# ICS.net
KiCad netlist of a schematic drawn in Altium Designer
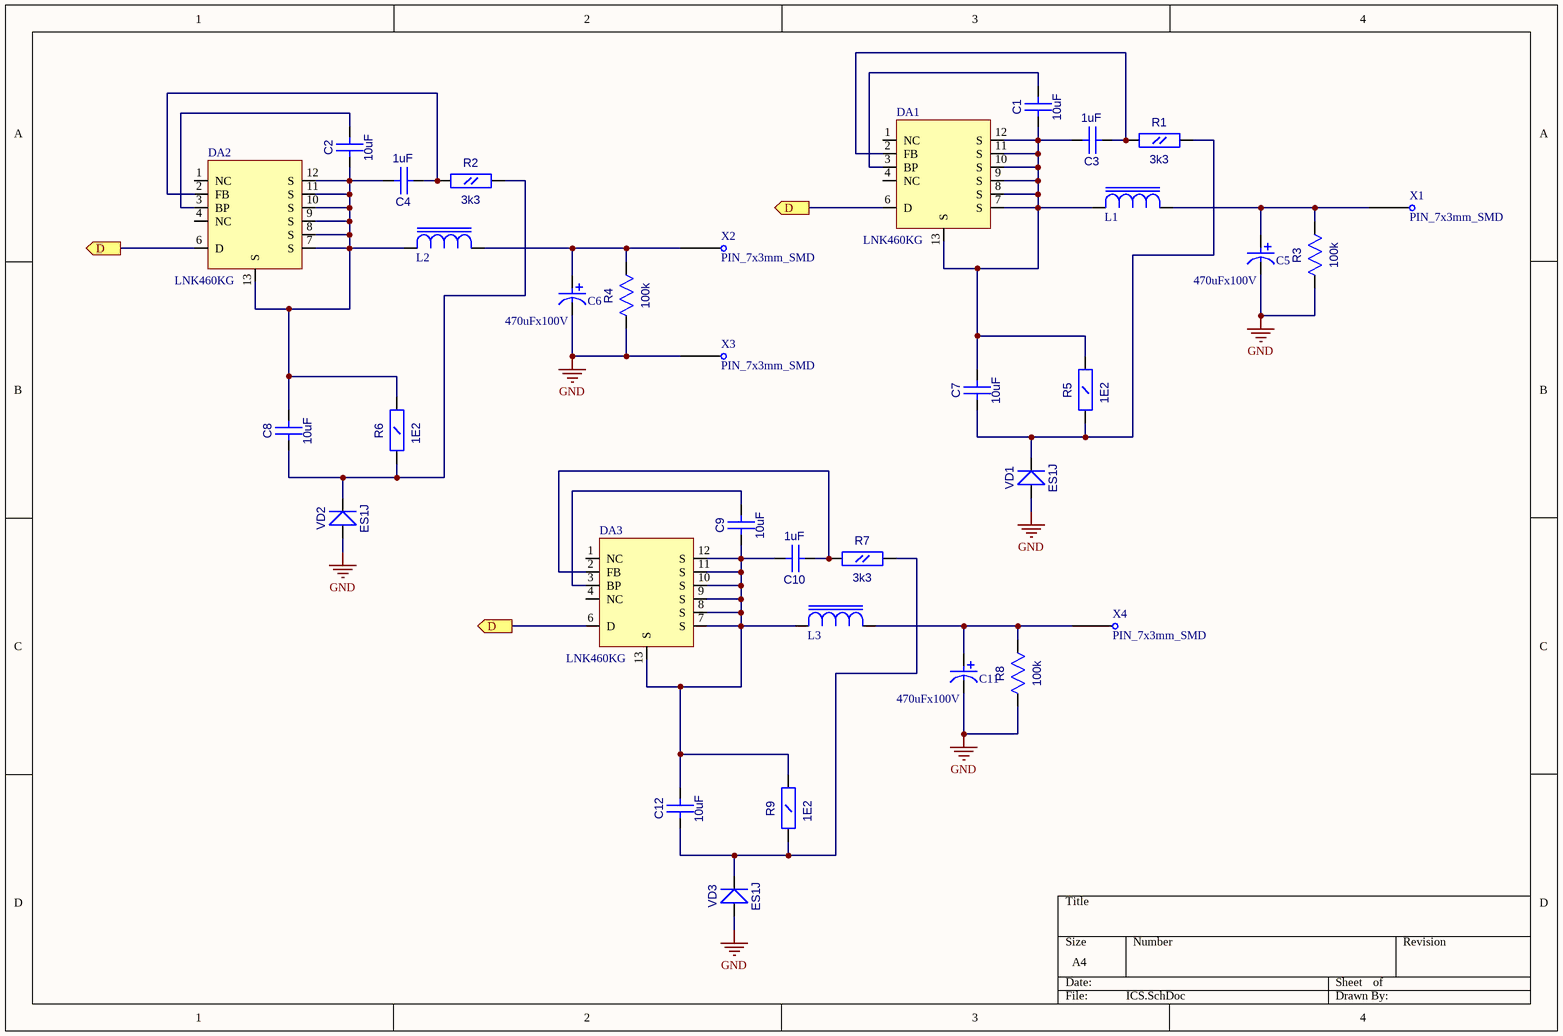
[diagram p0: ICS.SchDoc]

(export (version "E")
  (design (tool "Eeschema 10.0.6"))
  (components
    (comp (ref "C1")
      (value "10uF")
      (footprint "CC1206")
      (description "CC1206")
      (libsource (lib "gprs_modem_2") (part "CC1206"))
    )
    (comp (ref "C2")
      (value "10uF")
      (footprint "CC1206")
      (description "CC1206")
      (libsource (lib "gprs_modem_2") (part "CC1206"))
    )
    (comp (ref "C3")
      (value "1uF")
      (footprint "CC0805")
      (description "CC0805")
      (libsource (lib "gprs_modem_2") (part "CC0805"))
    )
    (comp (ref "C4")
      (value "1uF")
      (footprint "CC0805")
      (description "CC0805")
      (libsource (lib "gprs_modem_2") (part "CC0805"))
    )
    (comp (ref "C5")
      (value "470uFx100V")
      (footprint "CAP_7.5_SMD_2")
      (libsource (lib "gprs_modem_2") (part "CAP_16x25"))
    )
    (comp (ref "C6")
      (value "470uFx100V")
      (footprint "CAP_7.5_SMD_2")
      (libsource (lib "gprs_modem_2") (part "CAP_16x25"))
    )
    (comp (ref "C7")
      (value "10uF")
      (footprint "CC1206")
      (description "CC1206")
      (libsource (lib "gprs_modem_2") (part "CC1206"))
    )
    (comp (ref "C8")
      (value "10uF")
      (footprint "CC1206")
      (description "CC1206")
      (libsource (lib "gprs_modem_2") (part "CC1206"))
    )
    (comp (ref "C9")
      (value "10uF")
      (footprint "CC1206")
      (description "CC1206")
      (libsource (lib "gprs_modem_2") (part "CC1206"))
    )
    (comp (ref "C10")
      (value "1uF")
      (footprint "CC0805")
      (description "CC0805")
      (libsource (lib "gprs_modem_2") (part "CC0805"))
    )
    (comp (ref "C11")
      (value "470uFx100V")
      (footprint "CAP_7.5_SMD_2")
      (libsource (lib "gprs_modem_2") (part "CAP_16x25"))
    )
    (comp (ref "C12")
      (value "10uF")
      (footprint "CC1206")
      (description "CC1206")
      (libsource (lib "gprs_modem_2") (part "CC1206"))
    )
    (comp (ref "DA1")
      (value "LNK460KG")
      (footprint "eSOP-12")
      (libsource (lib "gprs_modem") (part "LNK460KG"))
    )
    (comp (ref "DA2")
      (value "LNK460KG")
      (footprint "eSOP-12")
      (libsource (lib "gprs_modem") (part "LNK460KG"))
    )
    (comp (ref "DA3")
      (value "LNK460KG")
      (footprint "eSOP-12")
      (libsource (lib "gprs_modem") (part "LNK460KG"))
    )
    (comp (ref "L1")
      (value "CDRH129HF-331MC")
      (footprint "IND_CDRH129")
      (libsource (lib "gprs_modem_2") (part "CDRH129"))
    )
    (comp (ref "L2")
      (value "CDRH129HF-331MC")
      (footprint "IND_CDRH129")
      (libsource (lib "gprs_modem_2") (part "CDRH129"))
    )
    (comp (ref "L3")
      (value "CDRH129HF-331MC")
      (footprint "IND_CDRH129")
      (libsource (lib "gprs_modem_2") (part "CDRH129"))
    )
    (comp (ref "R1")
      (value "3k3")
      (footprint "RC0805")
      (description "RC0805")
      (libsource (lib "gprs_modem_2") (part "RC0805"))
    )
    (comp (ref "R2")
      (value "3k3")
      (footprint "RC0805")
      (description "RC0805")
      (libsource (lib "gprs_modem_2") (part "RC0805"))
    )
    (comp (ref "R3")
      (value "100k")
      (footprint "RC0805")
      (description "RC0805")
      (libsource (lib "shlagbaum") (part "RC0805"))
    )
    (comp (ref "R4")
      (value "100k")
      (footprint "RC0805")
      (description "RC0805")
      (libsource (lib "shlagbaum") (part "RC0805"))
    )
    (comp (ref "R5")
      (value "1E2")
      (footprint "RC1206")
      (description "RC1206")
      (libsource (lib "gprs_modem_2") (part "RC1206"))
    )
    (comp (ref "R6")
      (value "1E2")
      (footprint "RC1206")
      (description "RC1206")
      (libsource (lib "gprs_modem_2") (part "RC1206"))
    )
    (comp (ref "R7")
      (value "3k3")
      (footprint "RC0805")
      (description "RC0805")
      (libsource (lib "gprs_modem_2") (part "RC0805"))
    )
    (comp (ref "R8")
      (value "100k")
      (footprint "RC0805")
      (description "RC0805")
      (libsource (lib "shlagbaum") (part "RC0805"))
    )
    (comp (ref "R9")
      (value "1E2")
      (footprint "RC1206")
      (description "RC1206")
      (libsource (lib "gprs_modem_2") (part "RC1206"))
    )
    (comp (ref "VD1")
      (value "ES1J")
      (footprint "SMA")
      (description "Schottky Rectifier")
      (libsource (lib "gprs_modem") (part "SS14"))
    )
    (comp (ref "VD2")
      (value "ES1J")
      (footprint "SMA")
      (description "Schottky Rectifier")
      (libsource (lib "gprs_modem") (part "SS14"))
    )
    (comp (ref "VD3")
      (value "ES1J")
      (footprint "SMA")
      (description "Schottky Rectifier")
      (libsource (lib "gprs_modem") (part "SS14"))
    )
    (comp (ref "X1")
      (value "PIN_7x3mm_SMD")
      (footprint "PIN_7x3mm_SMD")
      (libsource (lib "gprs_modem") (part "PIN_7x3mm_SMD"))
    )
    (comp (ref "X2")
      (value "PIN_7x3mm_SMD")
      (footprint "PIN_7x3mm_SMD")
      (libsource (lib "gprs_modem") (part "PIN_7x3mm_SMD"))
    )
    (comp (ref "X3")
      (value "PIN_7x3mm_SMD")
      (footprint "PIN_7x3mm_SMD")
      (libsource (lib "gprs_modem") (part "PIN_7x3mm_SMD"))
    )
    (comp (ref "X4")
      (value "PIN_7x3mm_SMD")
      (footprint "PIN_7x3mm_SMD")
      (libsource (lib "gprs_modem") (part "PIN_7x3mm_SMD"))
    )
  )
  (nets
    (net (code "1") (name "/D") (class "Default")
      (node (ref "DA1") (pin "6") (pinfunction "D_6") (pintype "passive"))
      (node (ref "DA2") (pin "6") (pinfunction "D_6") (pintype "passive"))
      (node (ref "DA3") (pin "6") (pinfunction "D_6") (pintype "passive"))
    )
    (net (code "2") (name "GND") (class "Default")
      (node (ref "C11") (pin "1") (pintype "passive"))
      (node (ref "C5") (pin "1") (pintype "passive"))
      (node (ref "C6") (pin "1") (pintype "passive"))
      (node (ref "R3") (pin "1") (pinfunction "A_1") (pintype "passive"))
      (node (ref "R4") (pin "1") (pinfunction "A_1") (pintype "passive"))
      (node (ref "R8") (pin "1") (pinfunction "A_1") (pintype "passive"))
      (node (ref "VD1") (pin "1") (pinfunction "A_1") (pintype "passive"))
      (node (ref "VD2") (pin "1") (pinfunction "A_1") (pintype "passive"))
      (node (ref "VD3") (pin "1") (pinfunction "A_1") (pintype "passive"))
      (node (ref "X3") (pin "1") (pinfunction "1_1") (pintype "passive"))
    )
    (net (code "3") (name "Net-(C1-A)") (class "Default")
      (node (ref "C1") (pin "1") (pinfunction "A_1") (pintype "passive"))
      (node (ref "C3") (pin "2") (pinfunction "B_2") (pintype "passive"))
      (node (ref "C7") (pin "2") (pinfunction "B_2") (pintype "passive"))
      (node (ref "DA1") (pin "10") (pinfunction "S_10") (pintype "passive"))
      (node (ref "DA1") (pin "11") (pinfunction "S_11") (pintype "passive"))
      (node (ref "DA1") (pin "12") (pinfunction "S_12") (pintype "passive"))
      (node (ref "DA1") (pin "13") (pinfunction "S_13") (pintype "passive"))
      (node (ref "DA1") (pin "7") (pinfunction "S_7") (pintype "passive"))
      (node (ref "DA1") (pin "8") (pinfunction "S_8") (pintype "passive"))
      (node (ref "DA1") (pin "9") (pinfunction "S_9") (pintype "passive"))
      (node (ref "L1") (pin "1") (pinfunction "A_1") (pintype "passive"))
      (node (ref "R5") (pin "2") (pinfunction "B_2") (pintype "passive"))
    )
    (net (code "4") (name "Net-(C1-B)") (class "Default")
      (node (ref "C1") (pin "2") (pinfunction "B_2") (pintype "passive"))
      (node (ref "DA1") (pin "3") (pinfunction "BP_3") (pintype "passive"))
    )
    (net (code "5") (name "Net-(C2-A)") (class "Default")
      (node (ref "C2") (pin "1") (pinfunction "A_1") (pintype "passive"))
      (node (ref "C4") (pin "2") (pinfunction "B_2") (pintype "passive"))
      (node (ref "C8") (pin "2") (pinfunction "B_2") (pintype "passive"))
      (node (ref "DA2") (pin "10") (pinfunction "S_10") (pintype "passive"))
      (node (ref "DA2") (pin "11") (pinfunction "S_11") (pintype "passive"))
      (node (ref "DA2") (pin "12") (pinfunction "S_12") (pintype "passive"))
      (node (ref "DA2") (pin "13") (pinfunction "S_13") (pintype "passive"))
      (node (ref "DA2") (pin "7") (pinfunction "S_7") (pintype "passive"))
      (node (ref "DA2") (pin "8") (pinfunction "S_8") (pintype "passive"))
      (node (ref "DA2") (pin "9") (pinfunction "S_9") (pintype "passive"))
      (node (ref "L2") (pin "1") (pinfunction "A_1") (pintype "passive"))
      (node (ref "R6") (pin "2") (pinfunction "B_2") (pintype "passive"))
    )
    (net (code "6") (name "Net-(C2-B)") (class "Default")
      (node (ref "C2") (pin "2") (pinfunction "B_2") (pintype "passive"))
      (node (ref "DA2") (pin "3") (pinfunction "BP_3") (pintype "passive"))
    )
    (net (code "7") (name "Net-(C3-A)") (class "Default")
      (node (ref "C3") (pin "1") (pinfunction "A_1") (pintype "passive"))
      (node (ref "DA1") (pin "2") (pinfunction "FB_2") (pintype "passive"))
      (node (ref "R1") (pin "1") (pinfunction "A_1") (pintype "passive"))
    )
    (net (code "8") (name "Net-(C4-A)") (class "Default")
      (node (ref "C4") (pin "1") (pinfunction "A_1") (pintype "passive"))
      (node (ref "DA2") (pin "2") (pinfunction "FB_2") (pintype "passive"))
      (node (ref "R2") (pin "1") (pinfunction "A_1") (pintype "passive"))
    )
    (net (code "9") (name "Net-(C7-A)") (class "Default")
      (node (ref "C7") (pin "1") (pinfunction "A_1") (pintype "passive"))
      (node (ref "R1") (pin "2") (pinfunction "B_2") (pintype "passive"))
      (node (ref "R5") (pin "1") (pinfunction "A_1") (pintype "passive"))
      (node (ref "VD1") (pin "2") (pinfunction "K_2") (pintype "passive"))
    )
    (net (code "10") (name "Net-(C8-A)") (class "Default")
      (node (ref "C8") (pin "1") (pinfunction "A_1") (pintype "passive"))
      (node (ref "R2") (pin "2") (pinfunction "B_2") (pintype "passive"))
      (node (ref "R6") (pin "1") (pinfunction "A_1") (pintype "passive"))
      (node (ref "VD2") (pin "2") (pinfunction "K_2") (pintype "passive"))
    )
    (net (code "11") (name "Net-(C9-B)") (class "Default")
      (node (ref "C9") (pin "2") (pinfunction "B_2") (pintype "passive"))
      (node (ref "DA3") (pin "3") (pinfunction "BP_3") (pintype "passive"))
    )
    (net (code "12") (name "Net-(C10-A)") (class "Default")
      (node (ref "C10") (pin "1") (pinfunction "A_1") (pintype "passive"))
      (node (ref "DA3") (pin "2") (pinfunction "FB_2") (pintype "passive"))
      (node (ref "R7") (pin "1") (pinfunction "A_1") (pintype "passive"))
    )
    (net (code "13") (name "Net-(C10-B)") (class "Default")
      (node (ref "C10") (pin "2") (pinfunction "B_2") (pintype "passive"))
      (node (ref "C12") (pin "2") (pinfunction "B_2") (pintype "passive"))
      (node (ref "C9") (pin "1") (pinfunction "A_1") (pintype "passive"))
      (node (ref "DA3") (pin "10") (pinfunction "S_10") (pintype "passive"))
      (node (ref "DA3") (pin "11") (pinfunction "S_11") (pintype "passive"))
      (node (ref "DA3") (pin "12") (pinfunction "S_12") (pintype "passive"))
      (node (ref "DA3") (pin "13") (pinfunction "S_13") (pintype "passive"))
      (node (ref "DA3") (pin "7") (pinfunction "S_7") (pintype "passive"))
      (node (ref "DA3") (pin "8") (pinfunction "S_8") (pintype "passive"))
      (node (ref "DA3") (pin "9") (pinfunction "S_9") (pintype "passive"))
      (node (ref "L3") (pin "1") (pinfunction "A_1") (pintype "passive"))
      (node (ref "R9") (pin "2") (pinfunction "B_2") (pintype "passive"))
    )
    (net (code "14") (name "Net-(C12-A)") (class "Default")
      (node (ref "C12") (pin "1") (pinfunction "A_1") (pintype "passive"))
      (node (ref "R7") (pin "2") (pinfunction "B_2") (pintype "passive"))
      (node (ref "R9") (pin "1") (pinfunction "A_1") (pintype "passive"))
      (node (ref "VD3") (pin "2") (pinfunction "K_2") (pintype "passive"))
    )
    (net (code "15") (name "Net-(L1-B)") (class "Default")
      (node (ref "C5") (pin "2") (pintype "passive"))
      (node (ref "L1") (pin "2") (pinfunction "B_2") (pintype "passive"))
      (node (ref "R3") (pin "2") (pinfunction "B_2") (pintype "passive"))
      (node (ref "X1") (pin "1") (pinfunction "1_1") (pintype "passive"))
    )
    (net (code "16") (name "Net-(L2-B)") (class "Default")
      (node (ref "C6") (pin "2") (pintype "passive"))
      (node (ref "L2") (pin "2") (pinfunction "B_2") (pintype "passive"))
      (node (ref "R4") (pin "2") (pinfunction "B_2") (pintype "passive"))
      (node (ref "X2") (pin "1") (pinfunction "1_1") (pintype "passive"))
    )
    (net (code "17") (name "Net-(L3-B)") (class "Default")
      (node (ref "C11") (pin "2") (pintype "passive"))
      (node (ref "L3") (pin "2") (pinfunction "B_2") (pintype "passive"))
      (node (ref "R8") (pin "2") (pinfunction "B_2") (pintype "passive"))
      (node (ref "X4") (pin "1") (pinfunction "1_1") (pintype "passive"))
    )
    (net (code "18") (name "unconnected-(DA1-NC-Pad1)") (class "Default")
      (node (ref "DA1") (pin "1") (pinfunction "NC_1") (pintype "passive"))
    )
    (net (code "19") (name "unconnected-(DA1-NC-Pad4)") (class "Default")
      (node (ref "DA1") (pin "4") (pinfunction "NC_4") (pintype "passive"))
    )
    (net (code "20") (name "unconnected-(DA2-NC-Pad1)") (class "Default")
      (node (ref "DA2") (pin "1") (pinfunction "NC_1") (pintype "passive"))
    )
    (net (code "21") (name "unconnected-(DA2-NC-Pad4)") (class "Default")
      (node (ref "DA2") (pin "4") (pinfunction "NC_4") (pintype "passive"))
    )
    (net (code "22") (name "unconnected-(DA3-NC-Pad1)") (class "Default")
      (node (ref "DA3") (pin "1") (pinfunction "NC_1") (pintype "passive"))
    )
    (net (code "23") (name "unconnected-(DA3-NC-Pad4)") (class "Default")
      (node (ref "DA3") (pin "4") (pinfunction "NC_4") (pintype "passive"))
    )
  )
)
